# STorM32_NT_ESP8266_module_v005.net
KiCad netlist of a schematic drawn in EAGLE
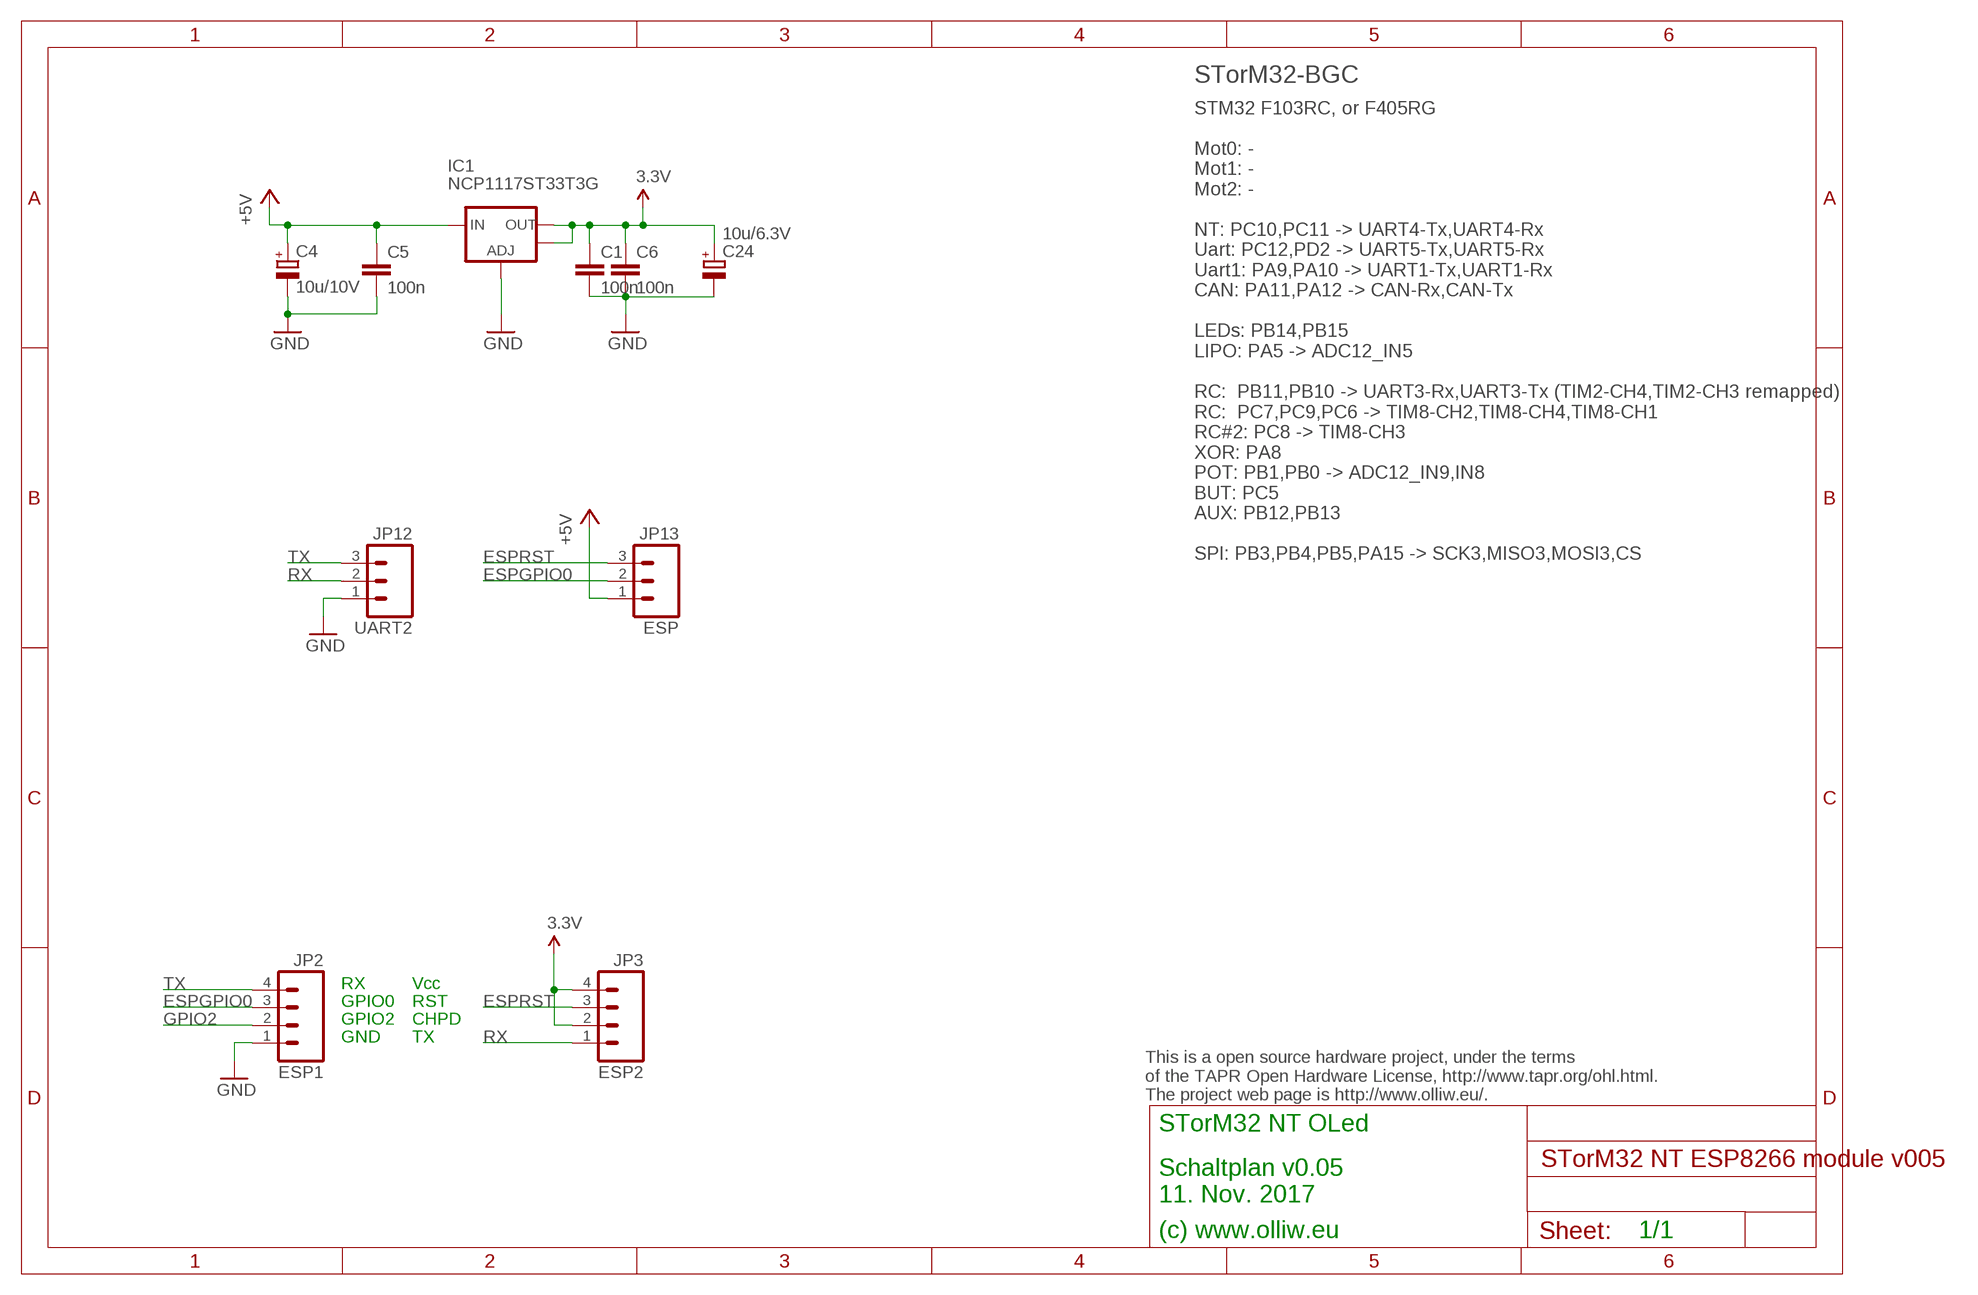
[diagram p0: schematic, sheet 1]

(export (version "E")
  (design (tool "Eeschema 10.0.6"))
  (components
    (comp (ref "C1")
      (value "100n")
      (footprint "eagle-import:C0603")
      (libsource (lib "eagle-import") (part "C-EUC0603"))
    )
    (comp (ref "C4")
      (value "10u/10V")
      (footprint "eagle-import:SMC_A")
      (libsource (lib "eagle-import") (part "CPOL-EUSMCA"))
    )
    (comp (ref "C5")
      (value "100n")
      (footprint "eagle-import:C0603")
      (libsource (lib "eagle-import") (part "C-EUC0603"))
    )
    (comp (ref "C6")
      (value "100n")
      (footprint "eagle-import:C0603")
      (libsource (lib "eagle-import") (part "C-EUC0603"))
    )
    (comp (ref "C24")
      (value "10u/6.3V")
      (footprint "eagle-import:SMC_B")
      (libsource (lib "eagle-import") (part "CPOL-EUSMCB"))
    )
    (comp (ref "IC1")
      (value "NCP1117ST33T3G")
      (footprint "eagle-import:SOT223")
      (libsource (lib "eagle-import") (part "V_REG_LM1117SOT223"))
    )
    (comp (ref "JP2")
      (value "ESP1")
      (footprint "eagle-import:1X04_NO_SILK")
      (libsource (lib "eagle-import") (part "M041X04_NO_SILK"))
    )
    (comp (ref "JP3")
      (value "ESP2")
      (footprint "eagle-import:1X04_NO_SILK")
      (libsource (lib "eagle-import") (part "M041X04_NO_SILK"))
    )
    (comp (ref "JP12")
      (value "UART2")
      (footprint "eagle-import:1X03_NO_SILK")
      (libsource (lib "eagle-import") (part "M031X03_NO_SILK"))
    )
    (comp (ref "JP13")
      (value "ESP")
      (footprint "eagle-import:1X03_NO_SILK")
      (libsource (lib "eagle-import") (part "M031X03_NO_SILK"))
    )
  )
  (nets
    (net (code "1") (name "+5V") (class "Default")
      (node (ref "C4") (pin "+") (pinfunction "+_+") (pintype "passive"))
      (node (ref "C5") (pin "1") (pinfunction "1_1") (pintype "passive"))
      (node (ref "IC1") (pin "3") (pinfunction "IN_3") (pintype "input"))
      (node (ref "JP13") (pin "1") (pinfunction "1_1") (pintype "passive"))
    )
    (net (code "2") (name "/ESPGPIO0") (class "Default")
      (node (ref "JP13") (pin "2") (pinfunction "2_2") (pintype "passive"))
      (node (ref "JP2") (pin "3") (pinfunction "3_3") (pintype "passive"))
    )
    (net (code "3") (name "/ESPRST") (class "Default")
      (node (ref "JP13") (pin "3") (pinfunction "3_3") (pintype "passive"))
      (node (ref "JP3") (pin "3") (pinfunction "3_3") (pintype "passive"))
    )
    (net (code "4") (name "/GPIO2") (class "Default")
      (node (ref "JP2") (pin "2") (pinfunction "2_2") (pintype "passive"))
    )
    (net (code "5") (name "/RX") (class "Default")
      (node (ref "JP12") (pin "2") (pinfunction "2_2") (pintype "passive"))
      (node (ref "JP3") (pin "1") (pinfunction "1_1") (pintype "passive"))
    )
    (net (code "6") (name "/TX") (class "Default")
      (node (ref "JP12") (pin "3") (pinfunction "3_3") (pintype "passive"))
      (node (ref "JP2") (pin "4") (pinfunction "4_4") (pintype "passive"))
    )
    (net (code "7") (name "3.3V") (class "Default")
      (node (ref "C1") (pin "1") (pinfunction "1_1") (pintype "passive"))
      (node (ref "C24") (pin "+") (pinfunction "+_+") (pintype "passive"))
      (node (ref "C6") (pin "1") (pinfunction "1_1") (pintype "passive"))
      (node (ref "IC1") (pin "2") (pinfunction "OUT_2") (pintype "output"))
      (node (ref "IC1") (pin "4") (pinfunction "OUT_4") (pintype "output"))
      (node (ref "JP3") (pin "2") (pinfunction "2_2") (pintype "passive"))
      (node (ref "JP3") (pin "4") (pinfunction "4_4") (pintype "passive"))
    )
    (net (code "8") (name "GND") (class "Default")
      (node (ref "C1") (pin "2") (pinfunction "2_2") (pintype "passive"))
      (node (ref "C24") (pin "-") (pinfunction "-_-") (pintype "passive"))
      (node (ref "C4") (pin "-") (pinfunction "-_-") (pintype "passive"))
      (node (ref "C5") (pin "2") (pinfunction "2_2") (pintype "passive"))
      (node (ref "C6") (pin "2") (pinfunction "2_2") (pintype "passive"))
      (node (ref "IC1") (pin "1") (pinfunction "ADJ_1") (pintype "input"))
      (node (ref "JP12") (pin "1") (pinfunction "1_1") (pintype "passive"))
      (node (ref "JP2") (pin "1") (pinfunction "1_1") (pintype "passive"))
    )
  )
)
